# Sheet5.net
KiCad netlist of a schematic drawn in Altium Designer
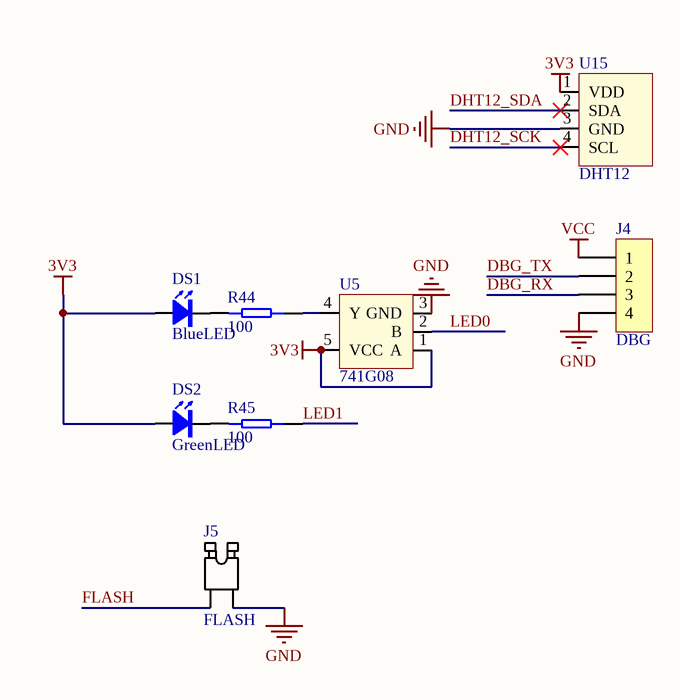
[diagram p0: Sheet5.SchDoc]

(export (version "E")
  (design (tool "Eeschema 10.0.6"))
  (components
    (comp (ref "DS1")
      (value "BlueLED")
      (footprint "LED-5")
      (description "Blue LED")
      (libsource (lib "Zero") (part "LED"))
    )
    (comp (ref "DS2")
      (value "GreenLED")
      (footprint "LED-5")
      (description "Green LED")
      (libsource (lib "Zero") (part "LED"))
    )
    (comp (ref "J4")
      (value "DBG")
      (footprint "SIP4-2.54")
      (description "jointbar")
      (libsource (lib "Zero") (part "SIP4"))
    )
    (comp (ref "J5") (value "FLASH") (footprint "CN2") (libsource (lib "My_Schlib") (part "CN2")))
    (comp (ref "R44") (value "100") (footprint "0402R") (libsource (lib "Zero") (part "R")))
    (comp (ref "R45") (value "100") (footprint "0402R") (libsource (lib "Zero") (part "R")))
    (comp (ref "U5")
      (value "741G08")
      (footprint "LC-SOT-23-5")
      (description "SN74AHC1G08DBVR")
      (libsource (lib "20180125H1") (part "741G08"))
    )
    (comp (ref "U15") (value "DHT12") (footprint "DHT12") (libsource (lib "20180125H1") (part "DHT12")))
  )
  (nets
    (net (code "1") (name "/DBG_RX") (class "Default")
      (node (ref "J4") (pin "3") (pinfunction "3_3") (pintype "passive"))
    )
    (net (code "2") (name "/DBG_TX") (class "Default")
      (node (ref "J4") (pin "2") (pinfunction "2_2") (pintype "passive"))
    )
    (net (code "3") (name "/DHT12_SCK") (class "Default")
      (node (ref "U15") (pin "4") (pinfunction "SCL_4") (pintype "passive+no_connect"))
    )
    (net (code "4") (name "/DHT12_SDA") (class "Default")
      (node (ref "U15") (pin "2") (pinfunction "SDA_2") (pintype "passive+no_connect"))
    )
    (net (code "5") (name "/FLASH") (class "Default")
      (node (ref "J5") (pin "1") (pinfunction "1_1") (pintype "passive"))
    )
    (net (code "6") (name "/LED0") (class "Default")
      (node (ref "U5") (pin "2") (pinfunction "B_2") (pintype "passive"))
    )
    (net (code "7") (name "/LED1") (class "Default")
      (node (ref "R45") (pin "2") (pinfunction "2_2") (pintype "passive"))
    )
    (net (code "8") (name "3V3") (class "Default")
      (node (ref "DS1") (pin "A") (pinfunction "1_A") (pintype "passive"))
      (node (ref "DS2") (pin "A") (pinfunction "1_A") (pintype "passive"))
      (node (ref "U15") (pin "1") (pinfunction "VDD_1") (pintype "passive"))
      (node (ref "U5") (pin "1") (pinfunction "A_1") (pintype "passive"))
      (node (ref "U5") (pin "5") (pinfunction "VCC_5") (pintype "passive"))
    )
    (net (code "9") (name "GND") (class "Default")
      (node (ref "J4") (pin "4") (pinfunction "4_4") (pintype "passive"))
      (node (ref "J5") (pin "2") (pinfunction "2_2") (pintype "passive"))
      (node (ref "U15") (pin "3") (pinfunction "GND_3") (pintype "passive"))
      (node (ref "U5") (pin "3") (pinfunction "GND_3") (pintype "passive"))
    )
    (net (code "10") (name "Net-(DS1-2)") (class "Default")
      (node (ref "DS1") (pin "K") (pinfunction "2_K") (pintype "passive"))
      (node (ref "R44") (pin "1") (pinfunction "1_1") (pintype "passive"))
    )
    (net (code "11") (name "Net-(DS2-2)") (class "Default")
      (node (ref "DS2") (pin "K") (pinfunction "2_K") (pintype "passive"))
      (node (ref "R45") (pin "1") (pinfunction "1_1") (pintype "passive"))
    )
    (net (code "12") (name "Net-(U5-Y)") (class "Default")
      (node (ref "R44") (pin "2") (pinfunction "2_2") (pintype "passive"))
      (node (ref "U5") (pin "4") (pinfunction "Y_4") (pintype "passive"))
    )
    (net (code "13") (name "VCC") (class "Default")
      (node (ref "J4") (pin "1") (pinfunction "1_1") (pintype "passive"))
    )
  )
)
